# mcu_valdis1.net
KiCad netlist of a schematic drawn in Altium Designer
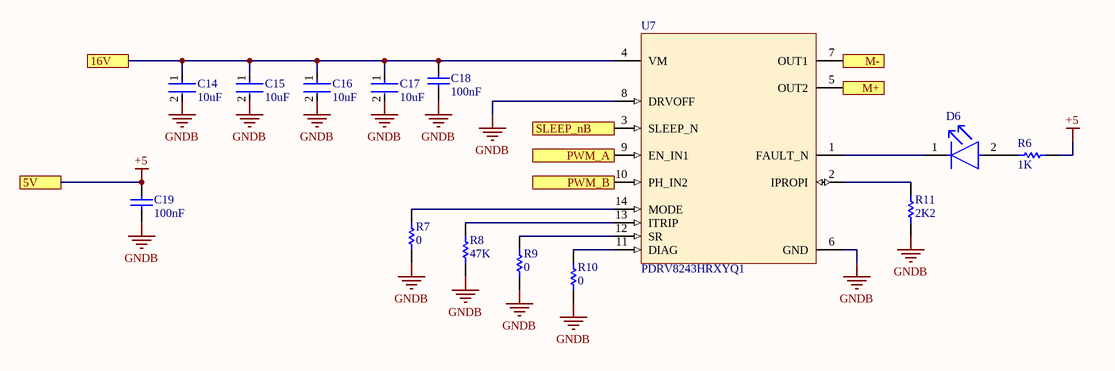
[diagram p0: mcu_valdis1.SchDoc]

(export (version "E")
  (design (tool "Eeschema 10.0.6"))
  (components
    (comp (ref "C14")
      (value "10uF")
      (footprint "FP-CL21-IPC_C")
      (description "CL21 Series 0805 22uF 25V ±20% Tolerance X5R Multilayer Ceramic Chip Capacitor")
      (libsource (lib "Altium Content Vault") (part "b4654b650e69147ec39a6b967a45e02"))
    )
    (comp (ref "C15")
      (value "10uF")
      (footprint "FP-CL21-IPC_C")
      (description "CL21 Series 0805 22uF 25V ±20% Tolerance X5R Multilayer Ceramic Chip Capacitor")
      (libsource (lib "Altium Content Vault") (part "b4654b650e69147ec39a6b967a45e02"))
    )
    (comp (ref "C16")
      (value "10uF")
      (footprint "FP-CL21-IPC_C")
      (description "CL21 Series 0805 22uF 25V ±20% Tolerance X5R Multilayer Ceramic Chip Capacitor")
      (libsource (lib "Altium Content Vault") (part "b4654b650e69147ec39a6b967a45e02"))
    )
    (comp (ref "C17")
      (value "10uF")
      (footprint "FP-CL21-IPC_C")
      (description "CL21 Series 0805 22uF 25V ±20% Tolerance X5R Multilayer Ceramic Chip Capacitor")
      (libsource (lib "Altium Content Vault") (part "b4654b650e69147ec39a6b967a45e02"))
    )
    (comp (ref "C18")
      (value "100nF")
      (footprint "CAPC1608X90X35ML10T15")
      (description "Chip Capacitor, 22 pF, +/- 5%, 50 V, -55 to 125 degC, 0603 (1608 Metric), RoHS, Tape and Reel")
      (fields (field (name "MANUFACTURER") "Murata"))
      (libsource (lib "Altium Content Vault") (part "CAP-NP-2"))
    )
    (comp (ref "C19")
      (value "100nF")
      (footprint "CAPC1608X90X35ML10T15")
      (description "Chip Capacitor, 22 pF, +/- 5%, 50 V, -55 to 125 degC, 0603 (1608 Metric), RoHS, Tape and Reel")
      (fields (field (name "MANUFACTURER") "Murata"))
      (libsource (lib "Altium Content Vault") (part "CAP-NP-2"))
    )
    (comp (ref "D6")
      (value "LTST-C191TBKT")
      (footprint "FP-LTST-C191TBKT-MFG")
      (description "LED BLUE CLEAR CHIP SMD")
      (libsource (lib "Altium Content Vault") (part "8706943c75ba83719d021d2fdc84c58"))
    )
    (comp (ref "R6")
      (value "1K")
      (footprint "RESC1609X50X30NL8T20")
      (description "Chip Resistor, 0 Ohm, Jumper, 100 mW, -55 to 155 degC, 0603 (1608 Metric), RoHS, Tape and Reel")
      (fields (field (name "MANUFACTURER") "Vishay Semiconductor"))
      (libsource (lib "Altium Content Vault") (part "RES-2"))
    )
    (comp (ref "R7")
      (value "0")
      (footprint "RESC1609X50X30NL8T20")
      (description "Chip Resistor, 0 Ohm, Jumper, 100 mW, -55 to 155 degC, 0603 (1608 Metric), RoHS, Tape and Reel")
      (fields (field (name "MANUFACTURER") "Vishay Semiconductor"))
      (libsource (lib "Altium Content Vault") (part "RES-2"))
    )
    (comp (ref "R8")
      (value "47K")
      (footprint "RESC1609X50X30NL8T20")
      (description "Chip Resistor, 0 Ohm, Jumper, 100 mW, -55 to 155 degC, 0603 (1608 Metric), RoHS, Tape and Reel")
      (fields (field (name "MANUFACTURER") "Vishay Semiconductor"))
      (libsource (lib "Altium Content Vault") (part "RES-2"))
    )
    (comp (ref "R9")
      (value "0")
      (footprint "RESC1609X50X30NL8T20")
      (description "Chip Resistor, 0 Ohm, Jumper, 100 mW, -55 to 155 degC, 0603 (1608 Metric), RoHS, Tape and Reel")
      (fields (field (name "MANUFACTURER") "Vishay Semiconductor"))
      (libsource (lib "Altium Content Vault") (part "RES-2"))
    )
    (comp (ref "R10")
      (value "0")
      (footprint "RESC1609X50X30NL8T20")
      (description "Chip Resistor, 0 Ohm, Jumper, 100 mW, -55 to 155 degC, 0603 (1608 Metric), RoHS, Tape and Reel")
      (fields (field (name "MANUFACTURER") "Vishay Semiconductor"))
      (libsource (lib "Altium Content Vault") (part "RES-2"))
    )
    (comp (ref "R11")
      (value "2K2")
      (footprint "RESC1609X50X30NL8T20")
      (description "Chip Resistor, 0 Ohm, Jumper, 100 mW, -55 to 155 degC, 0603 (1608 Metric), RoHS, Tape and Reel")
      (fields (field (name "MANUFACTURER") "Vishay Semiconductor"))
      (libsource (lib "Altium Content Vault") (part "RES-2"))
    )
    (comp (ref "U7")
      (value "PDRV8243HRXYQ1")
      (footprint "RXY0014A-MFG")
      (description "No Description Available")
      (fields (field (name "COPYRIGHT") "Copyright (C) 2022 Ultra Librarian. All rights reserved."))
      (libsource (lib "Valdis_Components") (part "PDRV8243HRXYQ1"))
    )
  )
  (nets
    (net (code "1") (name "+5") (class "Default")
      (node (ref "C19") (pin "2") (pinfunction "2_2") (pintype "passive"))
      (node (ref "R6") (pin "2") (pinfunction "2_2") (pintype "passive"))
    )
    (net (code "2") (name "/16V") (class "Default")
      (node (ref "C14") (pin "1") (pinfunction "1_1") (pintype "passive"))
      (node (ref "C15") (pin "1") (pinfunction "1_1") (pintype "passive"))
      (node (ref "C16") (pin "1") (pinfunction "1_1") (pintype "passive"))
      (node (ref "C17") (pin "1") (pinfunction "1_1") (pintype "passive"))
      (node (ref "C18") (pin "2") (pinfunction "2_2") (pintype "passive"))
      (node (ref "U7") (pin "4") (pinfunction "VM_4") (pintype "power_in"))
    )
    (net (code "3") (name "/M+") (class "Default")
      (node (ref "U7") (pin "5") (pinfunction "OUT2_5") (pintype "passive"))
    )
    (net (code "4") (name "/M-") (class "Default")
      (node (ref "U7") (pin "7") (pinfunction "OUT1_7") (pintype "passive"))
    )
    (net (code "5") (name "/PWM_A") (class "Default")
      (node (ref "U7") (pin "9") (pinfunction "EN_IN1_9") (pintype "input"))
    )
    (net (code "6") (name "/PWM_B") (class "Default")
      (node (ref "U7") (pin "10") (pinfunction "PH_IN2_10") (pintype "input"))
    )
    (net (code "7") (name "/SLEEP_nB") (class "Default")
      (node (ref "U7") (pin "3") (pinfunction "SLEEP_N_3") (pintype "input"))
    )
    (net (code "8") (name "GNDB") (class "Default")
      (node (ref "C14") (pin "2") (pinfunction "2_2") (pintype "passive"))
      (node (ref "C15") (pin "2") (pinfunction "2_2") (pintype "passive"))
      (node (ref "C16") (pin "2") (pinfunction "2_2") (pintype "passive"))
      (node (ref "C17") (pin "2") (pinfunction "2_2") (pintype "passive"))
      (node (ref "C18") (pin "1") (pinfunction "1_1") (pintype "passive"))
      (node (ref "C19") (pin "1") (pinfunction "1_1") (pintype "passive"))
      (node (ref "R10") (pin "1") (pinfunction "1_1") (pintype "passive"))
      (node (ref "R11") (pin "1") (pinfunction "1_1") (pintype "passive"))
      (node (ref "R7") (pin "1") (pinfunction "1_1") (pintype "passive"))
      (node (ref "R8") (pin "1") (pinfunction "1_1") (pintype "passive"))
      (node (ref "R9") (pin "1") (pinfunction "1_1") (pintype "passive"))
      (node (ref "U7") (pin "6") (pinfunction "GND_6") (pintype "power_in"))
      (node (ref "U7") (pin "8") (pinfunction "DRVOFF_8") (pintype "input"))
    )
    (net (code "9") (name "Net-(D6-A)") (class "Default")
      (node (ref "D6") (pin "2") (pinfunction "A_2") (pintype "passive"))
      (node (ref "R6") (pin "1") (pinfunction "1_1") (pintype "passive"))
    )
    (net (code "10") (name "Net-(D6-C)") (class "Default")
      (node (ref "D6") (pin "1") (pinfunction "C_1") (pintype "passive"))
      (node (ref "U7") (pin "1") (pinfunction "FAULT_N_1") (pintype "open_collector"))
    )
    (net (code "11") (name "Net-(U7-DIAG)") (class "Default")
      (node (ref "R10") (pin "2") (pinfunction "2_2") (pintype "passive"))
      (node (ref "U7") (pin "11") (pinfunction "DIAG_11") (pintype "input"))
    )
    (net (code "12") (name "Net-(U7-IPROPI)") (class "Default")
      (node (ref "R11") (pin "2") (pinfunction "2_2") (pintype "passive"))
      (node (ref "U7") (pin "2") (pinfunction "IPROPI_2") (pintype "bidirectional"))
    )
    (net (code "13") (name "Net-(U7-ITRIP)") (class "Default")
      (node (ref "R8") (pin "2") (pinfunction "2_2") (pintype "passive"))
      (node (ref "U7") (pin "13") (pinfunction "ITRIP_13") (pintype "input"))
    )
    (net (code "14") (name "Net-(U7-MODE)") (class "Default")
      (node (ref "R7") (pin "2") (pinfunction "2_2") (pintype "passive"))
      (node (ref "U7") (pin "14") (pinfunction "MODE_14") (pintype "input"))
    )
    (net (code "15") (name "Net-(U7-SR)") (class "Default")
      (node (ref "R9") (pin "2") (pinfunction "2_2") (pintype "passive"))
      (node (ref "U7") (pin "12") (pinfunction "SR_12") (pintype "input"))
    )
  )
)
